# interface_dac_sma_feedback_3PS.net
KiCad netlist of a schematic drawn in EAGLE
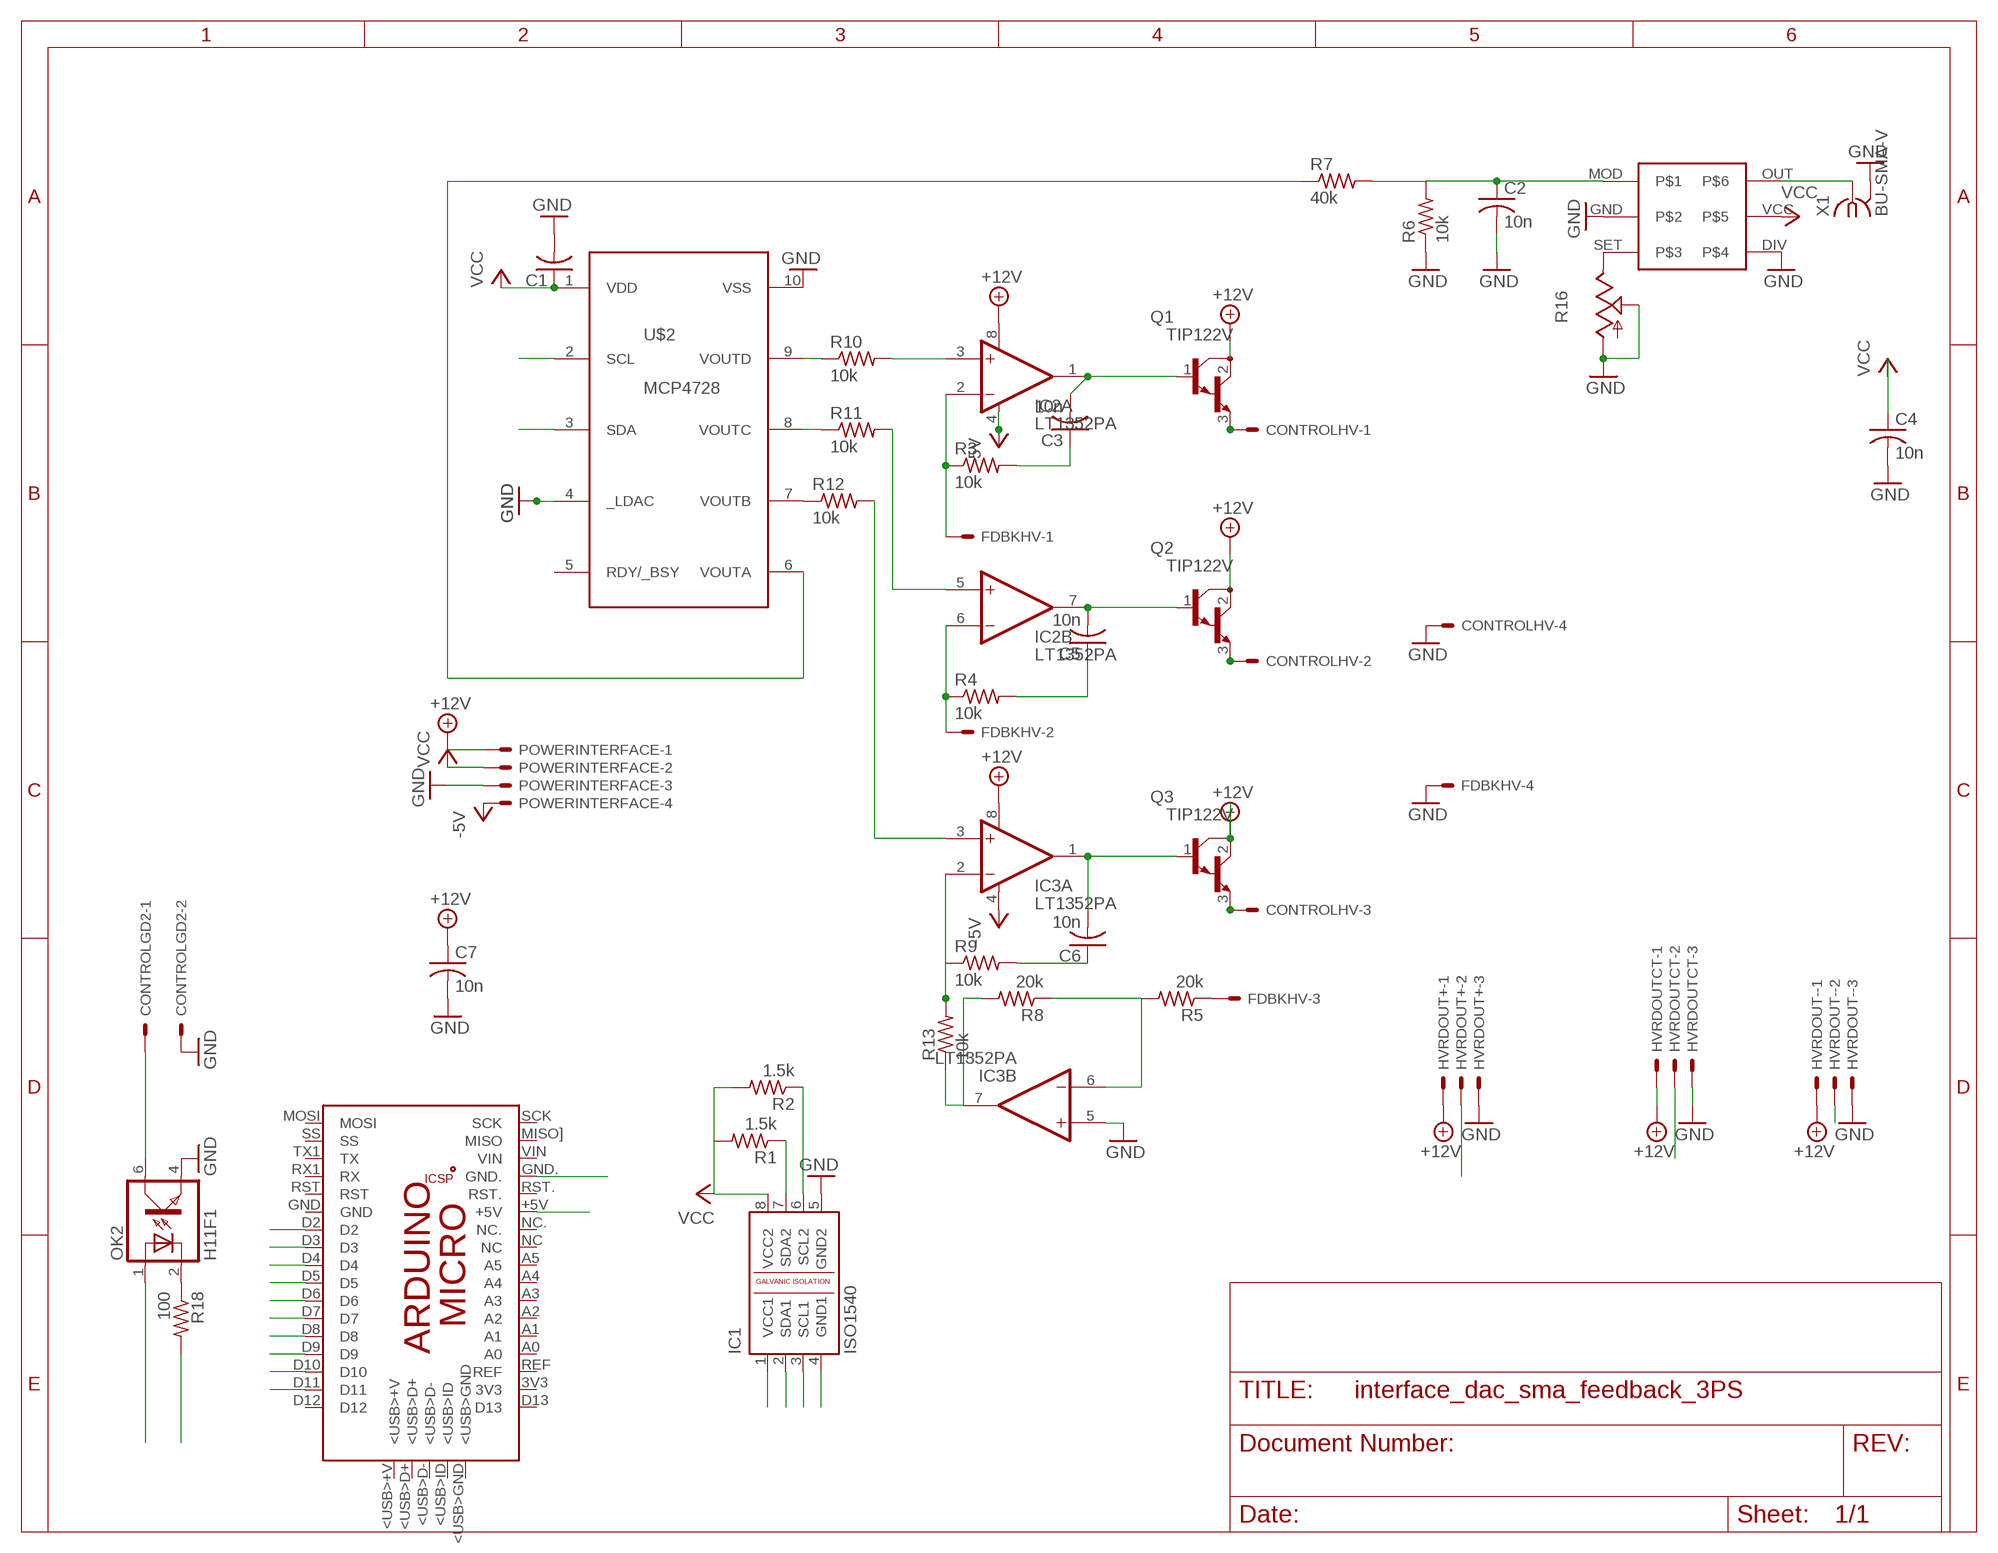
[diagram p0: schematic, sheet 1]

(export (version "E")
  (design (tool "Eeschema 10.0.6"))
  (components
    (comp (ref "C1")
      (value "C-US050-050X075")
      (footprint "eagle-import:C050-050X075")
      (libsource (lib "eagle-import") (part "C-US050-050X075"))
    )
    (comp (ref "C2")
      (value "10n")
      (footprint "eagle-import:C050-024X044")
      (libsource (lib "eagle-import") (part "resistor_C-US050-024X044"))
    )
    (comp (ref "C3")
      (value "10n")
      (footprint "eagle-import:C050-024X044")
      (libsource (lib "eagle-import") (part "resistor_C-US050-024X044"))
    )
    (comp (ref "C4")
      (value "10n")
      (footprint "eagle-import:C075-063X106")
      (libsource (lib "eagle-import") (part "resistor_C-US075-063X106"))
    )
    (comp (ref "C5")
      (value "10n")
      (footprint "eagle-import:C050-024X044")
      (libsource (lib "eagle-import") (part "resistor_C-US050-024X044"))
    )
    (comp (ref "C6")
      (value "10n")
      (footprint "eagle-import:C050-024X044")
      (libsource (lib "eagle-import") (part "resistor_C-US050-024X044"))
    )
    (comp (ref "C7")
      (value "10n")
      (footprint "eagle-import:C050-050X075")
      (libsource (lib "eagle-import") (part "resistor_C-US050-050X075"))
    )
    (comp (ref "CONTROLGD2")
      (value "KK-156-2")
      (footprint "eagle-import:KK-156-2")
      (libsource (lib "eagle-import") (part "KK-156-2"))
    )
    (comp (ref "CONTROLHV")
      (value "KK-156-4")
      (footprint "eagle-import:KK-156-4")
      (libsource (lib "eagle-import") (part "KK-156-4"))
    )
    (comp (ref "FDBKHV")
      (value "KK-156-4")
      (footprint "eagle-import:KK-156-4")
      (libsource (lib "eagle-import") (part "KK-156-4"))
    )
    (comp (ref "HVRDOUT+")
      (value "KK-156-3")
      (footprint "eagle-import:KK-156-3")
      (libsource (lib "eagle-import") (part "KK-156-3"))
    )
    (comp (ref "HVRDOUT-")
      (value "KK-156-3")
      (footprint "eagle-import:KK-156-3")
      (libsource (lib "eagle-import") (part "KK-156-3"))
    )
    (comp (ref "HVRDOUTCT")
      (value "KK-156-3")
      (footprint "eagle-import:KK-156-3")
      (libsource (lib "eagle-import") (part "KK-156-3"))
    )
    (comp (ref "IC1")
      (value "ISO1540")
      (footprint "eagle-import:DIL08")
      (libsource (lib "eagle-import") (part "ISO1540"))
    )
    (comp (ref "IC2")
      (value "LT1352PA")
      (footprint "eagle-import:DIL08")
      (libsource (lib "eagle-import") (part "LT1352PA"))
    )
    (comp (ref "IC3")
      (value "LT1352PA")
      (footprint "eagle-import:DIL08")
      (libsource (lib "eagle-import") (part "LT1352PA"))
    )
    (comp (ref "OK2")
      (value "H11F1")
      (footprint "eagle-import:DIL05")
      (libsource (lib "eagle-import") (part "H11F1"))
    )
    (comp (ref "PCB1")
      (value "ARDUINO_MICRO")
      (footprint "eagle-import:ARDUINO_MICRO")
      (libsource (lib "eagle-import") (part "ARDUINO_MICRO"))
    )
    (comp (ref "POWERINTERFACE")
      (value "KK-156-4")
      (footprint "eagle-import:KK-156-4")
      (libsource (lib "eagle-import") (part "KK-156-4"))
    )
    (comp (ref "Q1")
      (value "TIP122V")
      (footprint "eagle-import:TO220V")
      (libsource (lib "eagle-import") (part "TIP122V"))
    )
    (comp (ref "Q2")
      (value "TIP122V")
      (footprint "eagle-import:TO220V")
      (libsource (lib "eagle-import") (part "TIP122V"))
    )
    (comp (ref "Q3")
      (value "TIP122V")
      (footprint "eagle-import:TO220V")
      (libsource (lib "eagle-import") (part "TIP122V"))
    )
    (comp (ref "R1")
      (value "1.5k")
      (footprint "eagle-import:0207_12")
      (libsource (lib "eagle-import") (part "resistor_R-US_0207/12"))
    )
    (comp (ref "R2")
      (value "1.5k")
      (footprint "eagle-import:0207_12")
      (libsource (lib "eagle-import") (part "resistor_R-US_0207/12"))
    )
    (comp (ref "R3")
      (value "10k")
      (footprint "eagle-import:0207_12")
      (libsource (lib "eagle-import") (part "resistor_R-US_0207/12"))
    )
    (comp (ref "R4")
      (value "10k")
      (footprint "eagle-import:0207_12")
      (libsource (lib "eagle-import") (part "resistor_R-US_0207/12"))
    )
    (comp (ref "R5")
      (value "20k")
      (footprint "eagle-import:0207_12")
      (libsource (lib "eagle-import") (part "resistor_R-US_0207/12"))
    )
    (comp (ref "R6")
      (value "10k")
      (footprint "eagle-import:0207_12")
      (libsource (lib "eagle-import") (part "resistor_R-US_0207/12"))
    )
    (comp (ref "R7")
      (value "40k")
      (footprint "eagle-import:0207_12")
      (libsource (lib "eagle-import") (part "resistor_R-US_0207/12"))
    )
    (comp (ref "R8")
      (value "20k")
      (footprint "eagle-import:0207_12")
      (libsource (lib "eagle-import") (part "resistor_R-US_0207/12"))
    )
    (comp (ref "R9")
      (value "10k")
      (footprint "eagle-import:0207_12")
      (libsource (lib "eagle-import") (part "resistor_R-US_0207/12"))
    )
    (comp (ref "R10")
      (value "10k")
      (footprint "eagle-import:0207_12")
      (libsource (lib "eagle-import") (part "resistor_R-US_0207/12"))
    )
    (comp (ref "R11")
      (value "10k")
      (footprint "eagle-import:0207_12")
      (libsource (lib "eagle-import") (part "resistor_R-US_0207/12"))
    )
    (comp (ref "R12")
      (value "10k")
      (footprint "eagle-import:0207_12")
      (libsource (lib "eagle-import") (part "resistor_R-US_0207/12"))
    )
    (comp (ref "R13")
      (value "10k")
      (footprint "eagle-import:0207_12")
      (libsource (lib "eagle-import") (part "resistor_R-US_0207/12"))
    )
    (comp (ref "R16")
      (value "TRIM_US-B90P")
      (footprint "eagle-import:SP19L")
      (libsource (lib "eagle-import") (part "TRIM_US-B90P"))
    )
    (comp (ref "R18")
      (value "100")
      (footprint "eagle-import:0207_12")
      (libsource (lib "eagle-import") (part "R-US_0207/12"))
    )
    (comp (ref "U$1")
      (value "LTC6992")
      (footprint "eagle-import:DIL06")
      (libsource (lib "eagle-import") (part "LTC6992"))
    )
    (comp (ref "U$2")
      (value "MCP4728DIL")
      (footprint "eagle-import:DIL10")
      (libsource (lib "eagle-import") (part "MCP4728DIL"))
    )
    (comp (ref "X1")
      (value "BU-SMA-V")
      (footprint "eagle-import:BU-SMA-V")
      (libsource (lib "eagle-import") (part "BU-SMA-V"))
    )
  )
  (nets
    (net (code "1") (name "+12V") (class "Default")
      (node (ref "C7") (pin "1") (pinfunction "1_1") (pintype "passive"))
      (node (ref "HVRDOUT+") (pin "1") (pinfunction "S_1") (pintype "passive"))
      (node (ref "HVRDOUT-") (pin "1") (pinfunction "S_1") (pintype "passive"))
      (node (ref "HVRDOUTCT") (pin "1") (pinfunction "S_1") (pintype "passive"))
      (node (ref "IC2") (pin "8") (pinfunction "V+_8") (pintype "power_in"))
      (node (ref "IC3") (pin "8") (pinfunction "V+_8") (pintype "power_in"))
      (node (ref "POWERINTERFACE") (pin "1") (pinfunction "S_1") (pintype "passive"))
      (node (ref "Q1") (pin "2") (pinfunction "C_2") (pintype "passive"))
      (node (ref "Q2") (pin "2") (pinfunction "C_2") (pintype "passive"))
      (node (ref "Q3") (pin "2") (pinfunction "C_2") (pintype "passive"))
    )
    (net (code "2") (name "-5V") (class "Default")
      (node (ref "IC2") (pin "4") (pinfunction "V-_4") (pintype "power_in"))
      (node (ref "IC3") (pin "4") (pinfunction "V-_4") (pintype "power_in"))
      (node (ref "POWERINTERFACE") (pin "4") (pinfunction "S_4") (pintype "passive"))
    )
    (net (code "3") (name "/A+5") (class "Default")
      (node (ref "IC1") (pin "1") (pinfunction "VCC1_1") (pintype "input"))
      (node (ref "PCB1") (pin "+5V") (pinfunction "+5V_+5V") (pintype "bidirectional"))
    )
    (net (code "4") (name "/AGND") (class "Default")
      (node (ref "IC1") (pin "4") (pinfunction "GND1_4") (pintype "input"))
      (node (ref "PCB1") (pin "GND.") (pinfunction "GND._GND.") (pintype "bidirectional"))
      (node (ref "R18") (pin "2") (pinfunction "2_2") (pintype "passive"))
    )
    (net (code "5") (name "/N$2") (class "Default")
      (node (ref "C2") (pin "1") (pinfunction "1_1") (pintype "passive"))
      (node (ref "R6") (pin "2") (pinfunction "2_2") (pintype "passive"))
      (node (ref "R7") (pin "2") (pinfunction "2_2") (pintype "passive"))
      (node (ref "U$1") (pin "MOD") (pinfunction "P$1_MOD") (pintype "bidirectional"))
    )
    (net (code "6") (name "/N$6") (class "Default")
      (node (ref "FDBKHV") (pin "2") (pinfunction "S_2") (pintype "passive"))
      (node (ref "HVRDOUTCT") (pin "2") (pinfunction "S_2") (pintype "passive"))
      (node (ref "IC2") (pin "6") (pinfunction "-IN_6") (pintype "input"))
      (node (ref "R4") (pin "1") (pinfunction "1_1") (pintype "passive"))
    )
    (net (code "7") (name "/N$8") (class "Default")
      (node (ref "FDBKHV") (pin "1") (pinfunction "S_1") (pintype "passive"))
      (node (ref "HVRDOUT+") (pin "2") (pinfunction "S_2") (pintype "passive"))
      (node (ref "IC2") (pin "2") (pinfunction "-IN_2") (pintype "input"))
      (node (ref "R3") (pin "1") (pinfunction "1_1") (pintype "passive"))
    )
    (net (code "8") (name "/N$14") (class "Default")
      (node (ref "HVRDOUT-") (pin "2") (pinfunction "S_2") (pintype "passive"))
      (node (ref "IC3") (pin "7") (pinfunction "OUT_7") (pintype "output"))
      (node (ref "R13") (pin "1") (pinfunction "1_1") (pintype "passive"))
      (node (ref "R8") (pin "2") (pinfunction "2_2") (pintype "passive"))
    )
    (net (code "9") (name "/PWM9") (class "Default")
      (node (ref "OK2") (pin "1") (pinfunction "A_1") (pintype "passive"))
      (node (ref "PCB1") (pin "D9") (pinfunction "D9_D9") (pintype "bidirectional"))
    )
    (net (code "10") (name "/SCL") (class "Default")
      (node (ref "IC1") (pin "3") (pinfunction "SCL1_3") (pintype "input"))
      (node (ref "PCB1") (pin "D3") (pinfunction "D3_D3") (pintype "bidirectional"))
    )
    (net (code "11") (name "/SCL_OUT") (class "Default")
      (node (ref "IC1") (pin "6") (pinfunction "SCL2_6") (pintype "input"))
      (node (ref "R2") (pin "1") (pinfunction "1_1") (pintype "passive"))
      (node (ref "U$2") (pin "2") (pinfunction "SCL_2") (pintype "bidirectional"))
    )
    (net (code "12") (name "/SDA") (class "Default")
      (node (ref "IC1") (pin "2") (pinfunction "SDA1_2") (pintype "input"))
      (node (ref "PCB1") (pin "D2") (pinfunction "D2_D2") (pintype "bidirectional"))
    )
    (net (code "13") (name "/SDA_OUT") (class "Default")
      (node (ref "IC1") (pin "7") (pinfunction "SDA2_7") (pintype "input"))
      (node (ref "R1") (pin "1") (pinfunction "1_1") (pintype "passive"))
      (node (ref "U$2") (pin "3") (pinfunction "SDA_3") (pintype "bidirectional"))
    )
    (net (code "14") (name "GND") (class "Default")
      (node (ref "C1") (pin "2") (pinfunction "2_2") (pintype "passive"))
      (node (ref "C2") (pin "2") (pinfunction "2_2") (pintype "passive"))
      (node (ref "C4") (pin "2") (pinfunction "2_2") (pintype "passive"))
      (node (ref "C7") (pin "2") (pinfunction "2_2") (pintype "passive"))
      (node (ref "CONTROLGD2") (pin "2") (pinfunction "S_2") (pintype "passive"))
      (node (ref "CONTROLHV") (pin "4") (pinfunction "S_4") (pintype "passive"))
      (node (ref "FDBKHV") (pin "4") (pinfunction "S_4") (pintype "passive"))
      (node (ref "HVRDOUT+") (pin "3") (pinfunction "S_3") (pintype "passive"))
      (node (ref "HVRDOUT-") (pin "3") (pinfunction "S_3") (pintype "passive"))
      (node (ref "HVRDOUTCT") (pin "3") (pinfunction "S_3") (pintype "passive"))
      (node (ref "IC1") (pin "5") (pinfunction "GND2_5") (pintype "input"))
      (node (ref "IC3") (pin "5") (pinfunction "+IN_5") (pintype "input"))
      (node (ref "OK2") (pin "4") (pinfunction "EMIT_4") (pintype "passive"))
      (node (ref "POWERINTERFACE") (pin "3") (pinfunction "S_3") (pintype "passive"))
      (node (ref "R16") (pin "A") (pinfunction "A_A") (pintype "passive"))
      (node (ref "R16") (pin "S") (pinfunction "S_S") (pintype "passive"))
      (node (ref "R6") (pin "1") (pinfunction "1_1") (pintype "passive"))
      (node (ref "U$1") (pin "DIV") (pinfunction "P$4_DIV") (pintype "bidirectional"))
      (node (ref "U$1") (pin "GND") (pinfunction "P$2_GND") (pintype "bidirectional"))
      (node (ref "U$2") (pin "10") (pinfunction "VSS_10") (pintype "bidirectional"))
      (node (ref "U$2") (pin "4") (pinfunction "_LDAC_4") (pintype "bidirectional"))
      (node (ref "X1") (pin "2") (pinfunction "2_2") (pintype "passive"))
      (node (ref "X1") (pin "3") (pinfunction "2_3") (pintype "passive"))
      (node (ref "X1") (pin "4") (pinfunction "2_4") (pintype "passive"))
      (node (ref "X1") (pin "5") (pinfunction "2_5") (pintype "passive"))
    )
    (net (code "15") (name "Net-(C3-Pad1)") (class "Default")
      (node (ref "C3") (pin "1") (pinfunction "1_1") (pintype "passive"))
      (node (ref "R3") (pin "2") (pinfunction "2_2") (pintype "passive"))
    )
    (net (code "16") (name "Net-(C5-Pad1)") (class "Default")
      (node (ref "C5") (pin "1") (pinfunction "1_1") (pintype "passive"))
      (node (ref "R4") (pin "2") (pinfunction "2_2") (pintype "passive"))
    )
    (net (code "17") (name "Net-(C6-Pad1)") (class "Default")
      (node (ref "C6") (pin "1") (pinfunction "1_1") (pintype "passive"))
      (node (ref "R9") (pin "2") (pinfunction "2_2") (pintype "passive"))
    )
    (net (code "18") (name "Net-(CONTROLGD2A-S)") (class "Default")
      (node (ref "CONTROLGD2") (pin "1") (pinfunction "S_1") (pintype "passive"))
      (node (ref "OK2") (pin "6") (pinfunction "COL_6") (pintype "passive"))
    )
    (net (code "19") (name "Net-(CONTROLHVA-S)") (class "Default")
      (node (ref "CONTROLHV") (pin "1") (pinfunction "S_1") (pintype "passive"))
      (node (ref "Q1") (pin "3") (pinfunction "E_3") (pintype "passive"))
    )
    (net (code "20") (name "Net-(CONTROLHVB-S)") (class "Default")
      (node (ref "CONTROLHV") (pin "2") (pinfunction "S_2") (pintype "passive"))
      (node (ref "Q2") (pin "3") (pinfunction "E_3") (pintype "passive"))
    )
    (net (code "21") (name "Net-(CONTROLHVC-S)") (class "Default")
      (node (ref "CONTROLHV") (pin "3") (pinfunction "S_3") (pintype "passive"))
      (node (ref "Q3") (pin "3") (pinfunction "E_3") (pintype "passive"))
    )
    (net (code "22") (name "Net-(FDBKHVC-S)") (class "Default")
      (node (ref "FDBKHV") (pin "3") (pinfunction "S_3") (pintype "passive"))
      (node (ref "R5") (pin "1") (pinfunction "1_1") (pintype "passive"))
    )
    (net (code "23") (name "Net-(IC2A-+IN)") (class "Default")
      (node (ref "IC2") (pin "3") (pinfunction "+IN_3") (pintype "input"))
      (node (ref "R10") (pin "2") (pinfunction "2_2") (pintype "passive"))
    )
    (net (code "24") (name "Net-(IC2A-OUT)") (class "Default")
      (node (ref "C3") (pin "2") (pinfunction "2_2") (pintype "passive"))
      (node (ref "IC2") (pin "1") (pinfunction "OUT_1") (pintype "output"))
      (node (ref "Q1") (pin "1") (pinfunction "B_1") (pintype "passive"))
    )
    (net (code "25") (name "Net-(IC2B-+IN)") (class "Default")
      (node (ref "IC2") (pin "5") (pinfunction "+IN_5") (pintype "input"))
      (node (ref "R11") (pin "2") (pinfunction "2_2") (pintype "passive"))
    )
    (net (code "26") (name "Net-(IC2B-OUT)") (class "Default")
      (node (ref "C5") (pin "2") (pinfunction "2_2") (pintype "passive"))
      (node (ref "IC2") (pin "7") (pinfunction "OUT_7") (pintype "output"))
      (node (ref "Q2") (pin "1") (pinfunction "B_1") (pintype "passive"))
    )
    (net (code "27") (name "Net-(IC3A-+IN)") (class "Default")
      (node (ref "IC3") (pin "3") (pinfunction "+IN_3") (pintype "input"))
      (node (ref "R12") (pin "2") (pinfunction "2_2") (pintype "passive"))
    )
    (net (code "28") (name "Net-(IC3A--IN)") (class "Default")
      (node (ref "IC3") (pin "2") (pinfunction "-IN_2") (pintype "input"))
      (node (ref "R13") (pin "2") (pinfunction "2_2") (pintype "passive"))
      (node (ref "R9") (pin "1") (pinfunction "1_1") (pintype "passive"))
    )
    (net (code "29") (name "Net-(IC3A-OUT)") (class "Default")
      (node (ref "C6") (pin "2") (pinfunction "2_2") (pintype "passive"))
      (node (ref "IC3") (pin "1") (pinfunction "OUT_1") (pintype "output"))
      (node (ref "Q3") (pin "1") (pinfunction "B_1") (pintype "passive"))
    )
    (net (code "30") (name "Net-(IC3B--IN)") (class "Default")
      (node (ref "IC3") (pin "6") (pinfunction "-IN_6") (pintype "input"))
      (node (ref "R5") (pin "2") (pinfunction "2_2") (pintype "passive"))
      (node (ref "R8") (pin "1") (pinfunction "1_1") (pintype "passive"))
    )
    (net (code "31") (name "Net-(OK2-C)") (class "Default")
      (node (ref "OK2") (pin "2") (pinfunction "C_2") (pintype "passive"))
      (node (ref "R18") (pin "1") (pinfunction "1_1") (pintype "passive"))
    )
    (net (code "32") (name "Net-(U$1-P$3)") (class "Default")
      (node (ref "R16") (pin "E") (pinfunction "E_E") (pintype "passive"))
      (node (ref "U$1") (pin "SET") (pinfunction "P$3_SET") (pintype "bidirectional"))
    )
    (net (code "33") (name "Net-(U$1-P$6)") (class "Default")
      (node (ref "U$1") (pin "OUT") (pinfunction "P$6_OUT") (pintype "bidirectional"))
      (node (ref "X1") (pin "1") (pinfunction "1_1") (pintype "passive"))
    )
    (net (code "34") (name "Net-(U$2-VOUTA)") (class "Default")
      (node (ref "R7") (pin "1") (pinfunction "1_1") (pintype "passive"))
      (node (ref "U$2") (pin "6") (pinfunction "VOUTA_6") (pintype "bidirectional"))
    )
    (net (code "35") (name "Net-(U$2-VOUTB)") (class "Default")
      (node (ref "R12") (pin "1") (pinfunction "1_1") (pintype "passive"))
      (node (ref "U$2") (pin "7") (pinfunction "VOUTB_7") (pintype "bidirectional"))
    )
    (net (code "36") (name "Net-(U$2-VOUTC)") (class "Default")
      (node (ref "R11") (pin "1") (pinfunction "1_1") (pintype "passive"))
      (node (ref "U$2") (pin "8") (pinfunction "VOUTC_8") (pintype "bidirectional"))
    )
    (net (code "37") (name "Net-(U$2-VOUTD)") (class "Default")
      (node (ref "R10") (pin "1") (pinfunction "1_1") (pintype "passive"))
      (node (ref "U$2") (pin "9") (pinfunction "VOUTD_9") (pintype "bidirectional"))
    )
    (net (code "38") (name "VCC") (class "Default")
      (node (ref "C1") (pin "1") (pinfunction "1_1") (pintype "passive"))
      (node (ref "C4") (pin "1") (pinfunction "1_1") (pintype "passive"))
      (node (ref "IC1") (pin "8") (pinfunction "VCC2_8") (pintype "input"))
      (node (ref "POWERINTERFACE") (pin "2") (pinfunction "S_2") (pintype "passive"))
      (node (ref "R1") (pin "2") (pinfunction "2_2") (pintype "passive"))
      (node (ref "R2") (pin "2") (pinfunction "2_2") (pintype "passive"))
      (node (ref "U$1") (pin "VCC") (pinfunction "P$5_VCC") (pintype "bidirectional"))
      (node (ref "U$2") (pin "1") (pinfunction "VDD_1") (pintype "bidirectional"))
    )
    (net (code "39") (name "unconnected-(PCB1-MISO-PadMISO])") (class "Default")
      (node (ref "PCB1") (pin "MISO]") (pinfunction "MISO_MISO]") (pintype "bidirectional"))
    )
    (net (code "40") (name "unconnected-(PCB1-Pad3V3)") (class "Default")
      (node (ref "PCB1") (pin "3V3") (pinfunction "3V3_3V3") (pintype "bidirectional"))
    )
    (net (code "41") (name "unconnected-(PCB1-Pad5V)") (class "Default")
      (node (ref "PCB1") (pin "5V") (pinfunction "5V_5V") (pintype "bidirectional"))
    )
    (net (code "42") (name "unconnected-(PCB1-Pad<USB>+V)") (class "Default")
      (node (ref "PCB1") (pin "<USB>+V") (pinfunction "<USB>+V_<USB>+V") (pintype "bidirectional"))
    )
    (net (code "43") (name "unconnected-(PCB1-Pad<USB>D+)") (class "Default")
      (node (ref "PCB1") (pin "<USB>D+") (pinfunction "<USB>D+_<USB>D+") (pintype "bidirectional"))
    )
    (net (code "44") (name "unconnected-(PCB1-Pad<USB>D-)") (class "Default")
      (node (ref "PCB1") (pin "<USB>D-") (pinfunction "<USB>D-_<USB>D-") (pintype "bidirectional"))
    )
    (net (code "45") (name "unconnected-(PCB1-Pad<USB>GND)") (class "Default")
      (node (ref "PCB1") (pin "<USB>GND") (pinfunction "<USB>GND_<USB>GND") (pintype "bidirectional"))
    )
    (net (code "46") (name "unconnected-(PCB1-Pad<USB>ID)") (class "Default")
      (node (ref "PCB1") (pin "<USB>ID") (pinfunction "<USB>ID_<USB>ID") (pintype "bidirectional"))
    )
    (net (code "47") (name "unconnected-(PCB1-PadA0)") (class "Default")
      (node (ref "PCB1") (pin "A0") (pinfunction "A0_A0") (pintype "bidirectional"))
    )
    (net (code "48") (name "unconnected-(PCB1-PadA1)") (class "Default")
      (node (ref "PCB1") (pin "A1") (pinfunction "A1_A1") (pintype "bidirectional"))
    )
    (net (code "49") (name "unconnected-(PCB1-PadA2)") (class "Default")
      (node (ref "PCB1") (pin "A2") (pinfunction "A2_A2") (pintype "bidirectional"))
    )
    (net (code "50") (name "unconnected-(PCB1-PadA3)") (class "Default")
      (node (ref "PCB1") (pin "A3") (pinfunction "A3_A3") (pintype "bidirectional"))
    )
    (net (code "51") (name "unconnected-(PCB1-PadA4)") (class "Default")
      (node (ref "PCB1") (pin "A4") (pinfunction "A4_A4") (pintype "bidirectional"))
    )
    (net (code "52") (name "unconnected-(PCB1-PadA5)") (class "Default")
      (node (ref "PCB1") (pin "A5") (pinfunction "A5_A5") (pintype "bidirectional"))
    )
    (net (code "53") (name "unconnected-(PCB1-PadD4)") (class "Default")
      (node (ref "PCB1") (pin "D4") (pinfunction "D4_D4") (pintype "bidirectional"))
    )
    (net (code "54") (name "unconnected-(PCB1-PadD5)") (class "Default")
      (node (ref "PCB1") (pin "D5") (pinfunction "D5_D5") (pintype "bidirectional"))
    )
    (net (code "55") (name "unconnected-(PCB1-PadD6)") (class "Default")
      (node (ref "PCB1") (pin "D6") (pinfunction "D6_D6") (pintype "bidirectional"))
    )
    (net (code "56") (name "unconnected-(PCB1-PadD7)") (class "Default")
      (node (ref "PCB1") (pin "D7") (pinfunction "D7_D7") (pintype "bidirectional"))
    )
    (net (code "57") (name "unconnected-(PCB1-PadD8)") (class "Default")
      (node (ref "PCB1") (pin "D8") (pinfunction "D8_D8") (pintype "bidirectional"))
    )
    (net (code "58") (name "unconnected-(PCB1-PadD10)") (class "Default")
      (node (ref "PCB1") (pin "D10") (pinfunction "D10_D10") (pintype "bidirectional"))
    )
    (net (code "59") (name "unconnected-(PCB1-PadD11)") (class "Default")
      (node (ref "PCB1") (pin "D11") (pinfunction "D11_D11") (pintype "bidirectional"))
    )
    (net (code "60") (name "unconnected-(PCB1-PadD12)") (class "Default")
      (node (ref "PCB1") (pin "D12") (pinfunction "D12_D12") (pintype "bidirectional"))
    )
    (net (code "61") (name "unconnected-(PCB1-PadD13)") (class "Default")
      (node (ref "PCB1") (pin "D13") (pinfunction "D13_D13") (pintype "bidirectional"))
    )
    (net (code "62") (name "unconnected-(PCB1-PadGND)") (class "Default")
      (node (ref "PCB1") (pin "GND") (pinfunction "GND_GND") (pintype "bidirectional"))
    )
    (net (code "63") (name "unconnected-(PCB1-PadGND_)") (class "Default")
      (node (ref "PCB1") (pin "GND_") (pinfunction "GND__GND_") (pintype "bidirectional"))
    )
    (net (code "64") (name "unconnected-(PCB1-PadMISO.)") (class "Default")
      (node (ref "PCB1") (pin "MISO.") (pinfunction "MISO._MISO.") (pintype "bidirectional"))
    )
    (net (code "65") (name "unconnected-(PCB1-PadMOSI)") (class "Default")
      (node (ref "PCB1") (pin "MOSI") (pinfunction "MOSI_MOSI") (pintype "bidirectional"))
    )
    (net (code "66") (name "unconnected-(PCB1-PadMOSI.)") (class "Default")
      (node (ref "PCB1") (pin "MOSI.") (pinfunction "MOSI._MOSI.") (pintype "bidirectional"))
    )
    (net (code "67") (name "unconnected-(PCB1-PadNC)") (class "Default")
      (node (ref "PCB1") (pin "NC") (pinfunction "NC_NC") (pintype "bidirectional"))
    )
    (net (code "68") (name "unconnected-(PCB1-PadNC.)") (class "Default")
      (node (ref "PCB1") (pin "NC.") (pinfunction "NC._NC.") (pintype "bidirectional"))
    )
    (net (code "69") (name "unconnected-(PCB1-PadREF)") (class "Default")
      (node (ref "PCB1") (pin "REF") (pinfunction "REF_REF") (pintype "bidirectional"))
    )
    (net (code "70") (name "unconnected-(PCB1-PadRESET..)") (class "Default")
      (node (ref "PCB1") (pin "RESET..") (pinfunction "RESET.._RESET..") (pintype "bidirectional"))
    )
    (net (code "71") (name "unconnected-(PCB1-PadRST)") (class "Default")
      (node (ref "PCB1") (pin "RST") (pinfunction "RST_RST") (pintype "bidirectional"))
    )
    (net (code "72") (name "unconnected-(PCB1-PadRST.)") (class "Default")
      (node (ref "PCB1") (pin "RST.") (pinfunction "RST._RST.") (pintype "bidirectional"))
    )
    (net (code "73") (name "unconnected-(PCB1-PadSCK)") (class "Default")
      (node (ref "PCB1") (pin "SCK") (pinfunction "SCK_SCK") (pintype "bidirectional"))
    )
    (net (code "74") (name "unconnected-(PCB1-PadSCK.)") (class "Default")
      (node (ref "PCB1") (pin "SCK.") (pinfunction "SCK._SCK.") (pintype "bidirectional"))
    )
    (net (code "75") (name "unconnected-(PCB1-PadSS)") (class "Default")
      (node (ref "PCB1") (pin "SS") (pinfunction "SS_SS") (pintype "bidirectional"))
    )
    (net (code "76") (name "unconnected-(PCB1-PadVIN)") (class "Default")
      (node (ref "PCB1") (pin "VIN") (pinfunction "VIN_VIN") (pintype "bidirectional"))
    )
    (net (code "77") (name "unconnected-(PCB1-RX-PadRX1)") (class "Default")
      (node (ref "PCB1") (pin "RX1") (pinfunction "RX_RX1") (pintype "bidirectional"))
    )
    (net (code "78") (name "unconnected-(PCB1-TX-PadTX1)") (class "Default")
      (node (ref "PCB1") (pin "TX1") (pinfunction "TX_TX1") (pintype "bidirectional"))
    )
    (net (code "79") (name "unconnected-(U$2-RDY{slash}_BSY-Pad5)") (class "Default")
      (node (ref "U$2") (pin "5") (pinfunction "RDY/_BSY_5") (pintype "bidirectional"))
    )
  )
)
